# BSPD.net
KiCad netlist of a schematic drawn in Altium Designer
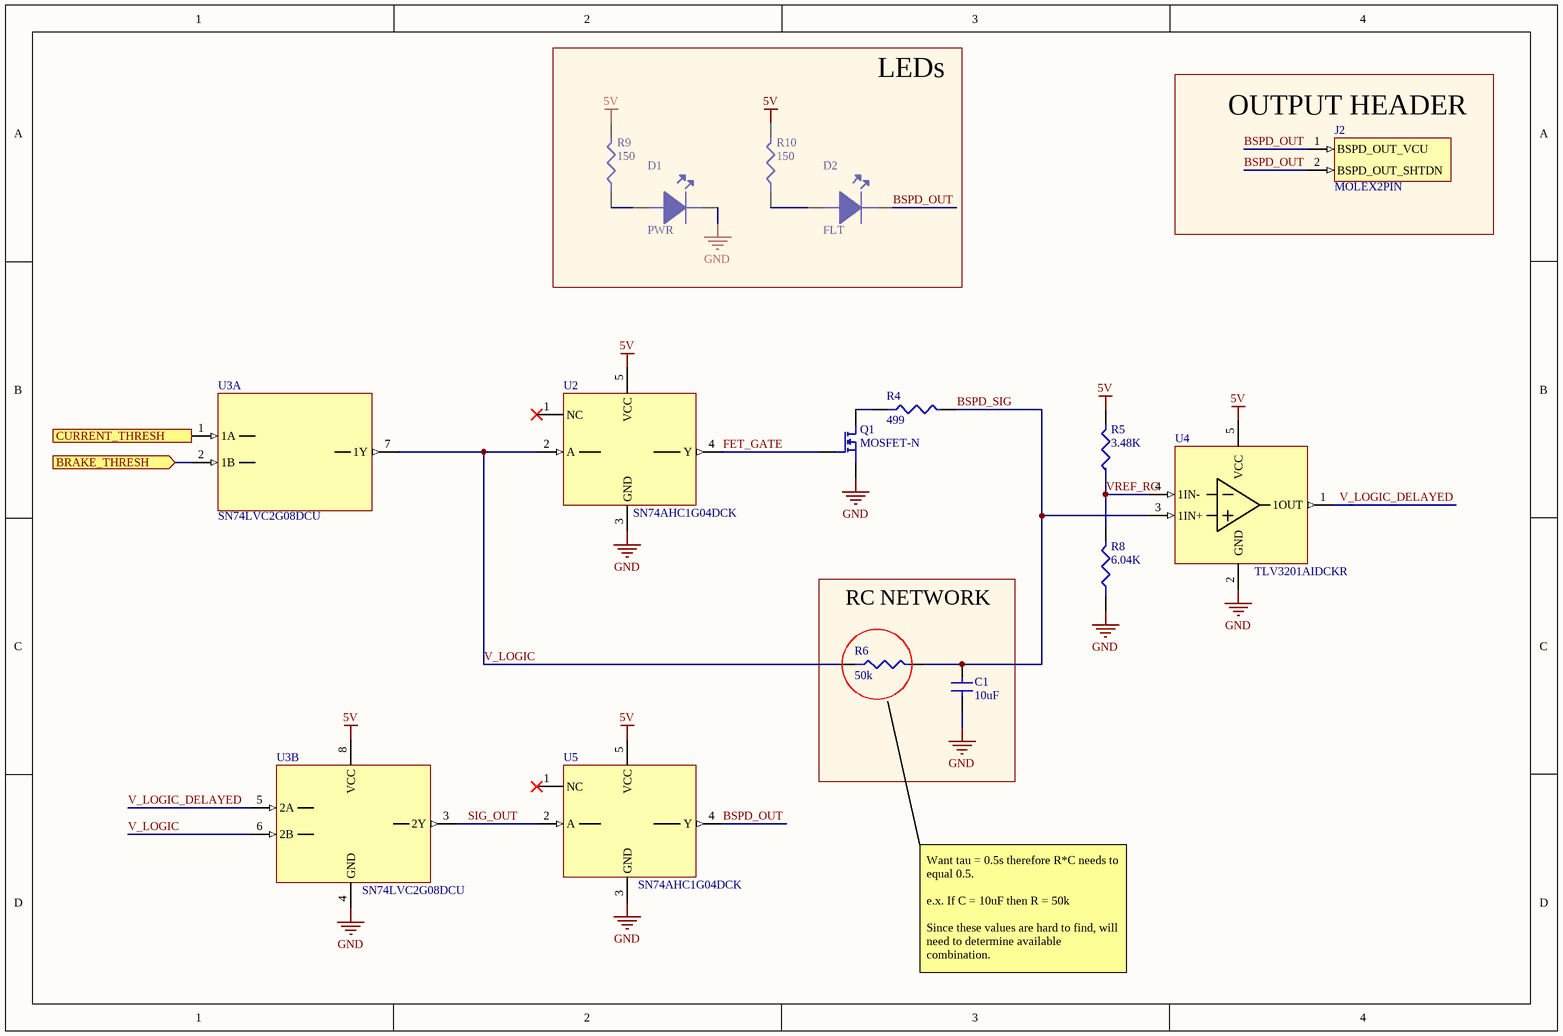
[diagram p0: BSPD.SchDoc]

(export (version "E")
  (design (tool "Eeschema 10.0.6"))
  (components
    (comp (ref "C1")
      (value "10uF")
      (footprint "C0805")
      (description "Cap Ceramic 10uF 10V X5R 10% SMD 0805 85C Embossed T/R")
      (fields
        (field (name "MANUFACTURER") "Samsung")
        (field (name "MANUFACTURER PART NUMBER") "CL21A106KPFNNNG")
      )
      (libsource (lib "BSPD") (part "CL21A106KPFNNNG"))
    )
    (comp (ref "D1")
      (value "PWR")
      (footprint "LED_0603")
      (description "LED GREEN CLEAR SMD")
      (fields
        (field (name "MANUFACTURER") "Vishay Lite-On")
        (field (name "MANUFACTURER PART NUMBER") "LTST-C191KGKT")
      )
      (libsource (lib "BSPD") (part "LTST-C191KGKT"))
    )
    (comp (ref "D2")
      (value "FLT")
      (footprint "LED_0603")
      (description "LED RED CLEAR SMD")
      (fields
        (field (name "MANUFACTURER") "Vishay Lite-On")
        (field (name "MANUFACTURER PART NUMBER") "LTST-C191KRKT")
      )
      (libsource (lib "BSPD") (part "LTST-C191KRKT"))
    )
    (comp (ref "J2")
      (value "MOLEX2PIN")
      (footprint "MOLEX_2PIN")
      (description "Headers & Wire Housings R/A HEADER 2 POS TIN SINGLE ROW")
      (fields (field (name "MANUFACTURER") "Molex") (field (name "MANUFACTURER PART NUMBER") "43650-0200"))
      (libsource (lib "BSPD") (part "43650-0200"))
    )
    (comp (ref "Q1")
      (value "MOSFET-N")
      (footprint "MOSFET")
      (description "MOSFET N-CH 50V 200MA SOT-23")
      (fields
        (field (name "MANUFACTURER") "ON Semiconductor")
        (field (name "MANUFACTURER PART NUMBER") "BSS138LT3G")
      )
      (libsource (lib "BSPD") (part "BSS138LT3G"))
    )
    (comp (ref "R4")
      (value "499")
      (footprint "R0805")
      (description "RES SMD 499 OHM 0.1% 1/8W 0805")
      (fields
        (field (name "MANUFACTURER") "Panasonic")
        (field (name "MANUFACTURER PART NUMBER") "ERA-6AEB4990V")
      )
      (libsource (lib "BSPD") (part "ERA-6AEB4990V"))
    )
    (comp (ref "R5")
      (value "3.48K")
      (footprint "R0805")
      (description "RES SMD 3.48K OHM 0.1% 1/8W 0805")
      (fields
        (field (name "MANUFACTURER") "Panasonic")
        (field (name "MANUFACTURER PART NUMBER") "ERA-6AEB3481V")
      )
      (libsource (lib "BSPD") (part "ERA-6AEB3481V"))
    )
    (comp (ref "R6")
      (value "50k")
      (footprint "RESC2013X12N")
      (description "RES 50K OHM 0.1% 1/5W 0805")
      (fields
        (field (name "MANUFACTURER") "Vishay")
        (field (name "MANUFACTURER PART NUMBER") "PTN0805E5002BST1")
      )
      (libsource (lib "BSPD") (part "PTN0805E5002BST1"))
    )
    (comp (ref "R8")
      (value "6.04K")
      (footprint "R0805")
      (description "RES SMD 6.04K OHM 0.1% 1/8W 0805")
      (fields
        (field (name "MANUFACTURER") "Panasonic")
        (field (name "MANUFACTURER PART NUMBER") "ERA6AEB6041V")
      )
      (libsource (lib "BSPD") (part "ERA6AEB6041V"))
    )
    (comp (ref "R9")
      (value "150")
      (footprint "RESC2012X07N")
      (description "RES SMD 150 OHM 1% 1/8W 0805")
      (fields
        (field (name "MANUFACTURER") "Panasonic")
        (field (name "MANUFACTURER PART NUMBER") "ERJ6ENF1500V")
      )
      (libsource (lib "BSPD") (part "ERJ6ENF1500V"))
    )
    (comp (ref "R10")
      (value "150")
      (footprint "RESC2012X07N")
      (description "RES SMD 150 OHM 1% 1/8W 0805")
      (fields
        (field (name "MANUFACTURER") "Panasonic")
        (field (name "MANUFACTURER PART NUMBER") "ERJ6ENF1500V")
      )
      (libsource (lib "BSPD") (part "ERJ6ENF1500V"))
    )
    (comp (ref "U2")
      (value "SN74AHC1G04DCK")
      (footprint "SN74AHC1G04DCK")
      (description "The SN74AHC1G04 contains one inverter gate. The\r\ndevice performs the Boolean function Y = A bar.")
      (fields
        (field (name "MANUFACTURER") "Texas Instruments")
        (field (name "MANUFACTURER PART NUMBER") "SN74AHC1G04DCKR")
      )
      (libsource (lib "BSPD") (part "SN74AHC1G04DCK"))
    )
    (comp (ref "U3")
      (value "SN74LVC2G08DCU")
      (footprint "SN74LVC2G08DCUR")
      (description "Dual 2-Input Positive-AND Gate")
      (libsource (lib "BSPD") (part "SN74LVC2G08DCUR"))
    )
    (comp (ref "U4")
      (value "TLV3201AIDCKR")
      (footprint "TLV3201AIDCK")
      (description "Comparator Single R-R I/P 5.5V 5-Pin SC-70 T/R")
      (fields (field (name "MANUFACTURER") "Texas Instruments"))
      (libsource (lib "BSPD") (part "TLV3201AIDCKR"))
    )
    (comp (ref "U5")
      (value "SN74AHC1G04DCK")
      (footprint "SN74AHC1G04DCK")
      (description "The SN74AHC1G04 contains one inverter gate. The\r\ndevice performs the Boolean function Y = A bar.")
      (fields
        (field (name "MANUFACTURER") "Texas Instruments")
        (field (name "MANUFACTURER PART NUMBER") "SN74AHC1G04DCKR")
      )
      (libsource (lib "BSPD") (part "SN74AHC1G04DCK"))
    )
  )
  (nets
    (net (code "1") (name "/BRAKE_THRESH") (class "Default")
      (node (ref "U3") (pin "2") (pinfunction "1B_2") (pintype "input"))
    )
    (net (code "2") (name "/BSPD_OUT") (class "Default")
      (node (ref "D2") (pin "2") (pinfunction "2_2") (pintype "passive"))
      (node (ref "J2") (pin "1") (pinfunction "BSPD_OUT_VCU_1") (pintype "input"))
      (node (ref "J2") (pin "2") (pinfunction "BSPD_OUT_SHTDN_2") (pintype "input"))
      (node (ref "U5") (pin "4") (pinfunction "Y_4") (pintype "output"))
    )
    (net (code "3") (name "/BSPD_SIG") (class "Default")
      (node (ref "C1") (pin "2") (pinfunction "2_2") (pintype "passive"))
      (node (ref "R4") (pin "2") (pinfunction "2_2") (pintype "passive"))
      (node (ref "R6") (pin "2") (pinfunction "2_2") (pintype "passive"))
      (node (ref "U4") (pin "3") (pinfunction "1IN+_3") (pintype "input"))
    )
    (net (code "4") (name "/CURRENT_THRESH") (class "Default")
      (node (ref "U3") (pin "1") (pinfunction "1A_1") (pintype "input"))
    )
    (net (code "5") (name "/FET_GATE") (class "Default")
      (node (ref "Q1") (pin "1") (pinfunction "1_1") (pintype "passive"))
      (node (ref "U2") (pin "4") (pinfunction "Y_4") (pintype "output"))
    )
    (net (code "6") (name "/SIG_OUT") (class "Default")
      (node (ref "U3") (pin "3") (pinfunction "2Y_3") (pintype "output"))
      (node (ref "U5") (pin "2") (pinfunction "A_2") (pintype "input"))
    )
    (net (code "7") (name "/VREF_RC") (class "Default")
      (node (ref "R5") (pin "1") (pinfunction "1_1") (pintype "passive"))
      (node (ref "R8") (pin "2") (pinfunction "2_2") (pintype "passive"))
      (node (ref "U4") (pin "4") (pinfunction "1IN-_4") (pintype "input"))
    )
    (net (code "8") (name "/V_LOGIC") (class "Default")
      (node (ref "R6") (pin "1") (pinfunction "1_1") (pintype "passive"))
      (node (ref "U2") (pin "2") (pinfunction "A_2") (pintype "input"))
      (node (ref "U3") (pin "6") (pinfunction "2B_6") (pintype "input"))
      (node (ref "U3") (pin "7") (pinfunction "1Y_7") (pintype "output"))
    )
    (net (code "9") (name "/V_LOGIC_DELAYED") (class "Default")
      (node (ref "U3") (pin "5") (pinfunction "2A_5") (pintype "input"))
      (node (ref "U4") (pin "1") (pinfunction "1OUT_1") (pintype "output"))
    )
    (net (code "10") (name "5V") (class "Default")
      (node (ref "R10") (pin "2") (pinfunction "2_2") (pintype "passive"))
      (node (ref "R5") (pin "2") (pinfunction "2_2") (pintype "passive"))
      (node (ref "R9") (pin "2") (pinfunction "2_2") (pintype "passive"))
      (node (ref "U2") (pin "5") (pinfunction "VCC_5") (pintype "power_in"))
      (node (ref "U3") (pin "8") (pinfunction "VCC_8") (pintype "power_in"))
      (node (ref "U4") (pin "5") (pinfunction "VCC_5") (pintype "power_in"))
      (node (ref "U5") (pin "5") (pinfunction "VCC_5") (pintype "power_in"))
    )
    (net (code "11") (name "GND") (class "Default")
      (node (ref "C1") (pin "1") (pinfunction "1_1") (pintype "passive"))
      (node (ref "D1") (pin "2") (pinfunction "2_2") (pintype "passive"))
      (node (ref "Q1") (pin "2") (pinfunction "2_2") (pintype "passive"))
      (node (ref "R8") (pin "1") (pinfunction "1_1") (pintype "passive"))
      (node (ref "U2") (pin "3") (pinfunction "GND_3") (pintype "power_in"))
      (node (ref "U3") (pin "4") (pinfunction "GND_4") (pintype "power_in"))
      (node (ref "U4") (pin "2") (pinfunction "GND_2") (pintype "power_in"))
      (node (ref "U5") (pin "3") (pinfunction "GND_3") (pintype "power_in"))
    )
    (net (code "12") (name "Net-(D1-Pad1)") (class "Default")
      (node (ref "D1") (pin "1") (pinfunction "1_1") (pintype "passive"))
      (node (ref "R9") (pin "1") (pinfunction "1_1") (pintype "passive"))
    )
    (net (code "13") (name "Net-(D2-Pad1)") (class "Default")
      (node (ref "D2") (pin "1") (pinfunction "1_1") (pintype "passive"))
      (node (ref "R10") (pin "1") (pinfunction "1_1") (pintype "passive"))
    )
    (net (code "14") (name "Net-(Q1-Pad3)") (class "Default")
      (node (ref "Q1") (pin "3") (pinfunction "3_3") (pintype "passive"))
      (node (ref "R4") (pin "1") (pinfunction "1_1") (pintype "passive"))
    )
    (net (code "15") (name "unconnected-(U2-NC-Pad1)") (class "Default")
      (node (ref "U2") (pin "1") (pinfunction "NC_1") (pintype "open_collector+no_connect"))
    )
    (net (code "16") (name "unconnected-(U5-NC-Pad1)") (class "Default")
      (node (ref "U5") (pin "1") (pinfunction "NC_1") (pintype "open_collector+no_connect"))
    )
  )
)
